# BPC_PWR_MCU.net
KiCad netlist of a schematic drawn in Altium Designer
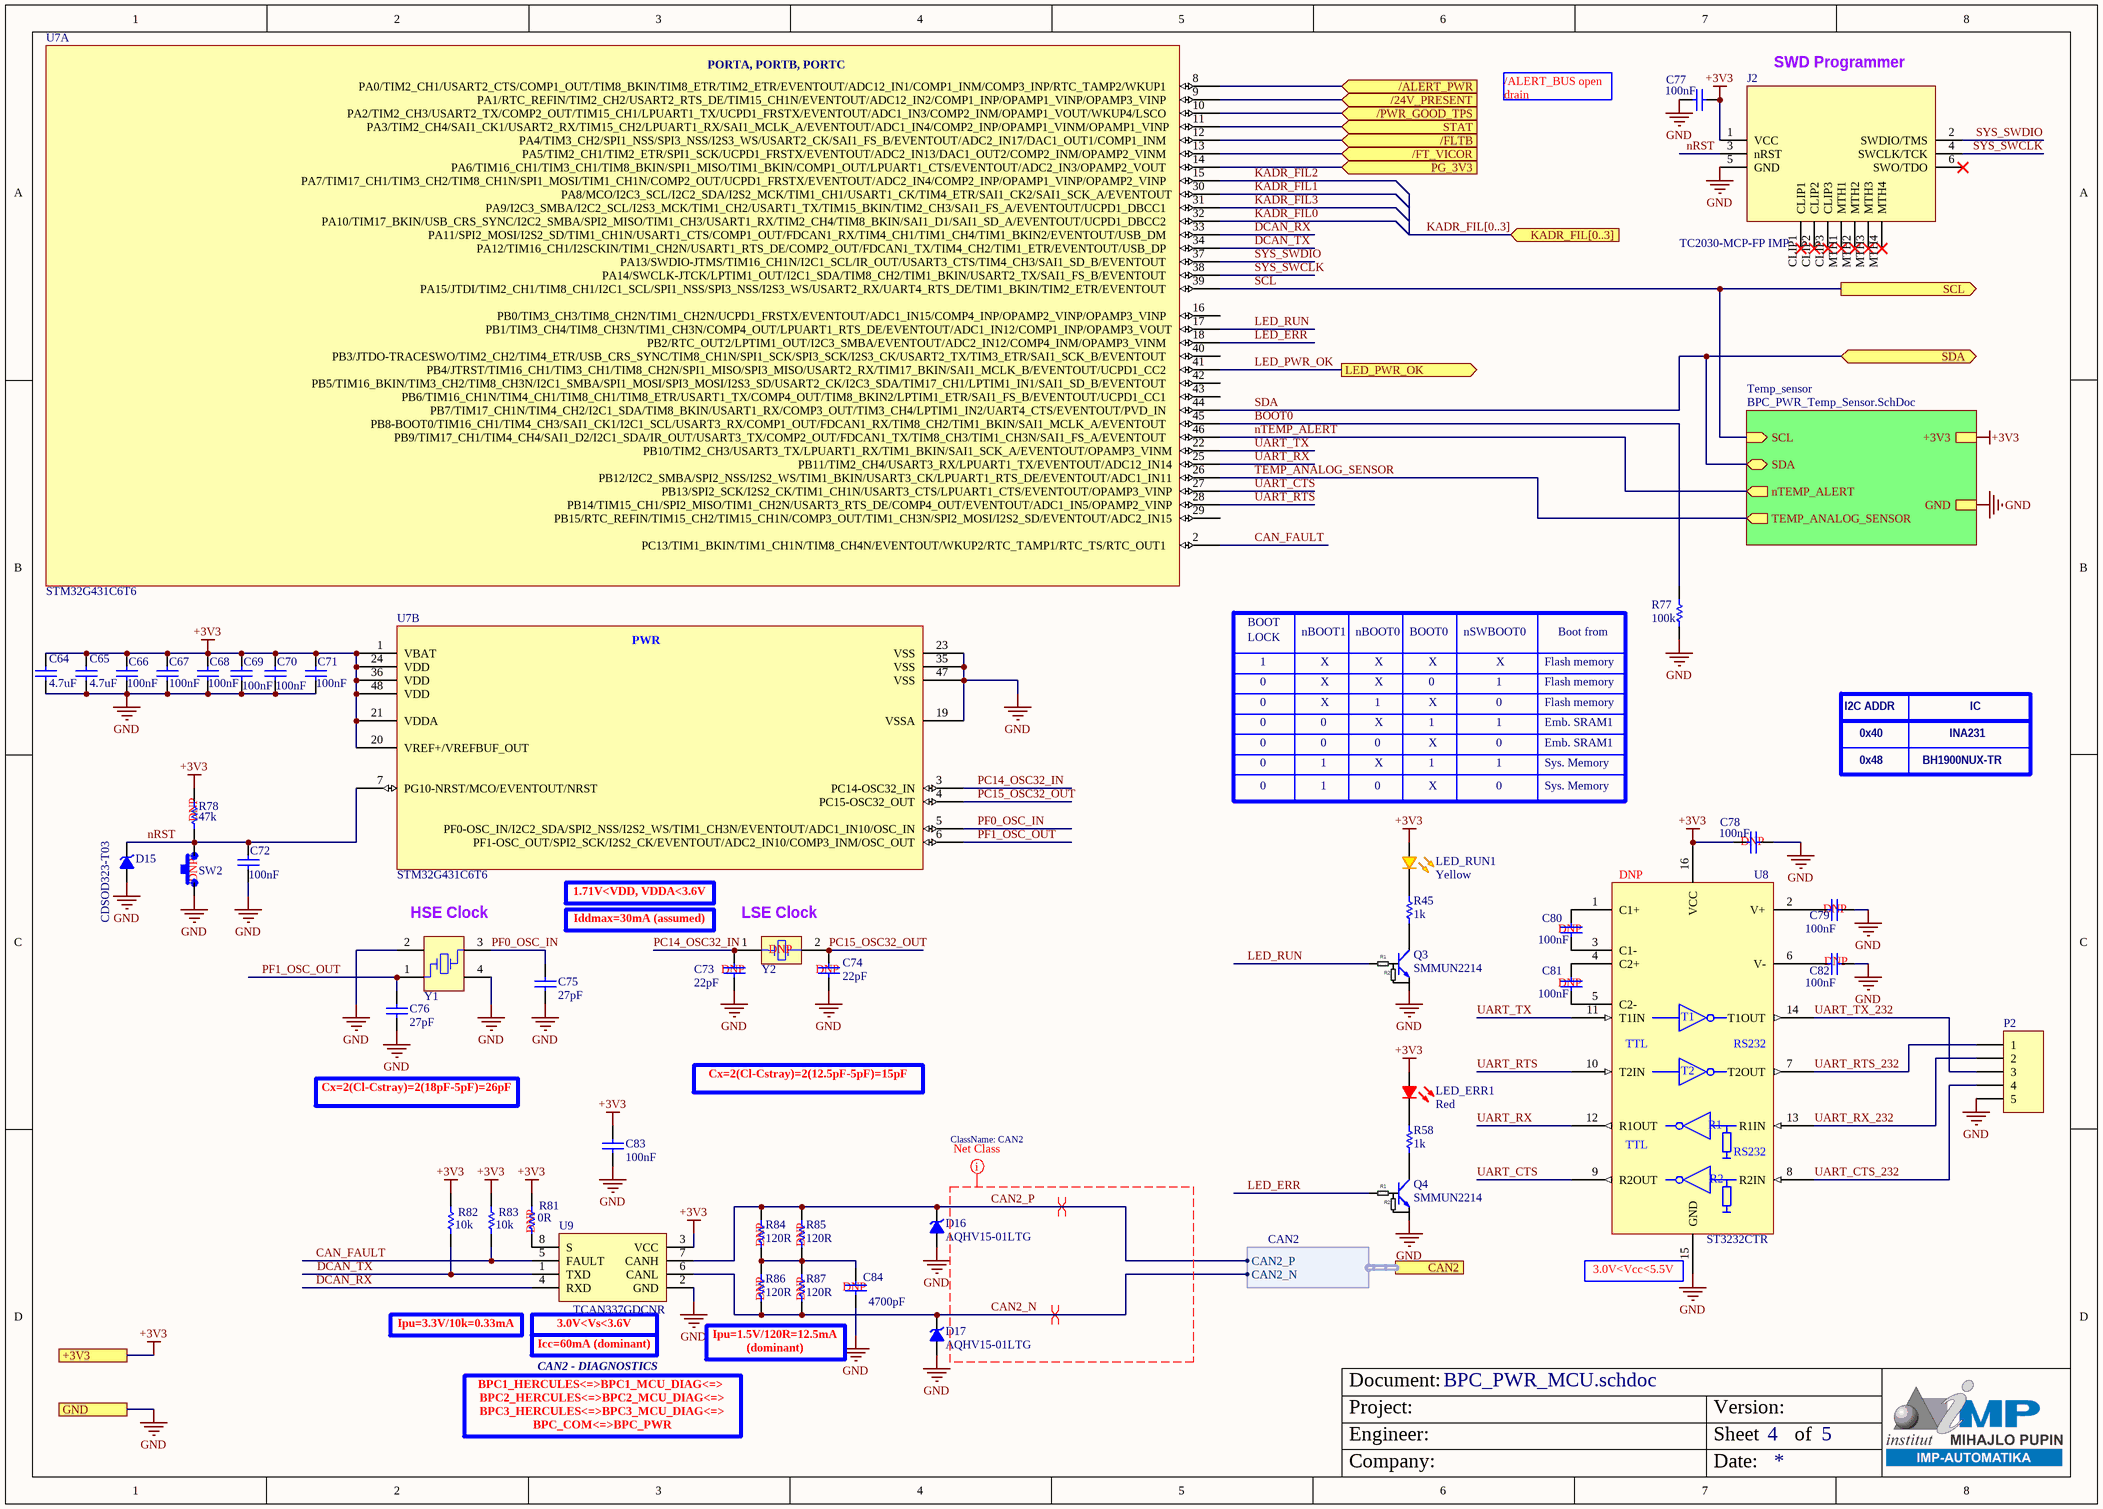
[diagram p0: BPC_PWR_MCU.schdoc]

(export (version "E")
  (design (tool "Eeschema 10.0.6"))
  (components
    (comp (ref "C64")
      (value "Ceramic Capacitor")
      (footprint "C0603L 0.8 MM MS")
      (description "Ceramic Capacitor 4.7uF 10V X5R 0603")
      (fields
        (field (name "DISTRIBUTOR PART NUMBER") "187-CL10A475KP8NNNC")
        (field (name "MANUFACTURER") "Samsung Electro-Mechanics")
        (field (name "DB PARAMETER 1") "4.7uF")
      )
      (libsource (lib "MS IMP Library") (part "Cap Cer 4.7uF 10V X5R 0603 MS"))
    )
    (comp (ref "C65")
      (value "Ceramic Capacitor")
      (footprint "C0603L 0.8 MM MS")
      (description "Ceramic Capacitor 4.7uF 10V X5R 0603")
      (fields
        (field (name "DISTRIBUTOR PART NUMBER") "187-CL10A475KP8NNNC")
        (field (name "MANUFACTURER") "Samsung Electro-Mechanics")
        (field (name "DB PARAMETER 1") "4.7uF")
      )
      (libsource (lib "MS IMP Library") (part "Cap Cer 4.7uF 10V X5R 0603 MS"))
    )
    (comp (ref "C66")
      (value "Ceramic Capacitor")
      (footprint "C0603L 0.8 MM MS")
      (description "Ceramic Capacitor 100nF 50V X7R 0603")
      (fields
        (field (name "DISTRIBUTOR PART NUMBER") "187-CL10B104KB8WPNC")
        (field (name "MANUFACTURER") "Samsung Electro-Mechanics")
        (field (name "CAPACITANCE") "100nF")
      )
      (libsource (lib "MS IMP Library") (part "Cap Cer 100nF 50V X7R 0603 Pt02"))
    )
    (comp (ref "C67")
      (value "Ceramic Capacitor")
      (footprint "C0603L 0.8 MM MS")
      (description "Ceramic Capacitor 100nF 50V X7R 0603")
      (fields
        (field (name "DISTRIBUTOR PART NUMBER") "187-CL10B104KB8WPNC")
        (field (name "MANUFACTURER") "Samsung Electro-Mechanics")
        (field (name "CAPACITANCE") "100nF")
      )
      (libsource (lib "MS IMP Library") (part "Cap Cer 100nF 50V X7R 0603 Pt02"))
    )
    (comp (ref "C68")
      (value "Ceramic Capacitor")
      (footprint "C0603L 0.8 MM MS")
      (description "Ceramic Capacitor 100nF 50V X7R 0603")
      (fields
        (field (name "DISTRIBUTOR PART NUMBER") "187-CL10B104KB8WPNC")
        (field (name "MANUFACTURER") "Samsung Electro-Mechanics")
        (field (name "CAPACITANCE") "100nF")
      )
      (libsource (lib "MS IMP Library") (part "Cap Cer 100nF 50V X7R 0603 Pt02"))
    )
    (comp (ref "C69")
      (value "Ceramic Capacitor")
      (footprint "C0603L 0.8 MM MS")
      (description "Ceramic Capacitor 100nF 50V X7R 0603")
      (fields
        (field (name "DISTRIBUTOR PART NUMBER") "187-CL10B104KB8WPNC")
        (field (name "MANUFACTURER") "Samsung Electro-Mechanics")
        (field (name "CAPACITANCE") "100nF")
      )
      (libsource (lib "MS IMP Library") (part "Cap Cer 100nF 50V X7R 0603 Pt02"))
    )
    (comp (ref "C70")
      (value "Ceramic Capacitor")
      (footprint "C0603L 0.8 MM MS")
      (description "Ceramic Capacitor 100nF 50V X7R 0603")
      (fields
        (field (name "DISTRIBUTOR PART NUMBER") "187-CL10B104KB8WPNC")
        (field (name "MANUFACTURER") "Samsung Electro-Mechanics")
        (field (name "CAPACITANCE") "100nF")
      )
      (libsource (lib "MS IMP Library") (part "Cap Cer 100nF 50V X7R 0603 Pt02"))
    )
    (comp (ref "C71")
      (value "Ceramic Capacitor")
      (footprint "C0603L 0.8 MM MS")
      (description "Ceramic Capacitor 100nF 50V X7R 0603")
      (fields
        (field (name "DISTRIBUTOR PART NUMBER") "187-CL10B104KB8WPNC")
        (field (name "MANUFACTURER") "Samsung Electro-Mechanics")
        (field (name "CAPACITANCE") "100nF")
      )
      (libsource (lib "MS IMP Library") (part "Cap Cer 100nF 50V X7R 0603 Pt02"))
    )
    (comp (ref "C72")
      (value "Ceramic Capacitor")
      (footprint "C0603L 0.8 MM MS")
      (description "Ceramic Capacitor 100nF 50V X7R 0603")
      (fields
        (field (name "DISTRIBUTOR PART NUMBER") "187-CL10B104KB8WPNC")
        (field (name "MANUFACTURER") "Samsung Electro-Mechanics")
        (field (name "CAPACITANCE") "100nF")
      )
      (libsource (lib "MS IMP Library") (part "Cap Cer 100nF 50V X7R 0603 Pt02"))
    )
    (comp (ref "C73")
      (value "Ceramic Capacitor")
      (footprint "C0603L 0.8 MM MS")
      (description "Ceramic Capacitor 22pF 50V C0G_NP0 0603")
      (fields
        (field (name "DISTRIBUTOR PART NUMBER") "478-1167-1-ND")
        (field (name "MANUFACTURER") "AVX Corporation")
        (field (name "POPULATED") "DNP")
        (field (name "CAPACITANCE") "22pF")
      )
      (libsource (lib "MS IMP Library") (part "Cap Cer 22pF 50V C0G_NP0 0603 MS"))
    )
    (comp (ref "C74")
      (value "Ceramic Capacitor")
      (footprint "C0603L 0.8 MM MS")
      (description "Ceramic Capacitor 22pF 50V C0G_NP0 0603")
      (fields
        (field (name "DISTRIBUTOR PART NUMBER") "478-1167-1-ND")
        (field (name "MANUFACTURER") "AVX Corporation")
        (field (name "POPULATED") "DNP")
        (field (name "CAPACITANCE") "22pF")
      )
      (libsource (lib "MS IMP Library") (part "Cap Cer 22pF 50V C0G_NP0 0603 MS"))
    )
    (comp (ref "C75")
      (value "Ceramic Capacitor")
      (footprint "C0603L 0.8 MM MS")
      (description "Ceramic Capacitor 27pF 50V C0G_NP0 0603")
      (fields
        (field (name "DISTRIBUTOR PART NUMBER") "311-1063-1-ND")
        (field (name "MANUFACTURER") "Yageo")
        (field (name "CAPACITANCE") "27pF")
      )
      (libsource (lib "MS IMP Library") (part "Cap Cer 27pF 50V C0G_NP0 0603 MS"))
    )
    (comp (ref "C76")
      (value "Ceramic Capacitor")
      (footprint "C0603L 0.8 MM MS")
      (description "Ceramic Capacitor 27pF 50V C0G_NP0 0603")
      (fields
        (field (name "DISTRIBUTOR PART NUMBER") "311-1063-1-ND")
        (field (name "MANUFACTURER") "Yageo")
        (field (name "CAPACITANCE") "27pF")
      )
      (libsource (lib "MS IMP Library") (part "Cap Cer 27pF 50V C0G_NP0 0603 MS"))
    )
    (comp (ref "C77")
      (value "Ceramic Capacitor")
      (footprint "C0603L 0.8 MM MS")
      (description "Ceramic Capacitor 100nF 50V X7R 0603")
      (fields
        (field (name "DISTRIBUTOR PART NUMBER") "187-CL10B104KB8WPNC")
        (field (name "MANUFACTURER") "Samsung Electro-Mechanics")
        (field (name "CAPACITANCE") "100nF")
      )
      (libsource (lib "MS IMP Library") (part "Cap Cer 100nF 50V X7R 0603 Pt02"))
    )
    (comp (ref "C78")
      (value "Ceramic Capacitor")
      (footprint "C0603L 0.8 MM MS")
      (description "Ceramic Capacitor 100nF 50V X7R 0603")
      (fields
        (field (name "DISTRIBUTOR PART NUMBER") "187-CL10B104KB8WPNC")
        (field (name "MANUFACTURER") "Samsung Electro-Mechanics")
        (field (name "POPULATED") "DNP")
        (field (name "CAPACITANCE") "100nF")
      )
      (libsource (lib "MS IMP Library") (part "Cap Cer 100nF 50V X7R 0603 Pt02"))
    )
    (comp (ref "C79")
      (value "Ceramic Capacitor")
      (footprint "C0603L 0.8 MM MS")
      (description "Ceramic Capacitor 100nF 50V X7R 0603")
      (fields
        (field (name "DISTRIBUTOR PART NUMBER") "187-CL10B104KB8WPNC")
        (field (name "MANUFACTURER") "Samsung Electro-Mechanics")
        (field (name "POPULATED") "DNP")
        (field (name "CAPACITANCE") "100nF")
      )
      (libsource (lib "MS IMP Library") (part "Cap Cer 100nF 50V X7R 0603 Pt02"))
    )
    (comp (ref "C80")
      (value "Ceramic Capacitor")
      (footprint "C0603L 0.8 MM MS")
      (description "Ceramic Capacitor 100nF 50V X7R 0603")
      (fields
        (field (name "DISTRIBUTOR PART NUMBER") "187-CL10B104KB8WPNC")
        (field (name "MANUFACTURER") "Samsung Electro-Mechanics")
        (field (name "POPULATED") "DNP")
        (field (name "CAPACITANCE") "100nF")
      )
      (libsource (lib "MS IMP Library") (part "Cap Cer 100nF 50V X7R 0603 Pt02"))
    )
    (comp (ref "C81")
      (value "Ceramic Capacitor")
      (footprint "C0603L 0.8 MM MS")
      (description "Ceramic Capacitor 100nF 50V X7R 0603")
      (fields
        (field (name "DISTRIBUTOR PART NUMBER") "187-CL10B104KB8WPNC")
        (field (name "MANUFACTURER") "Samsung Electro-Mechanics")
        (field (name "POPULATED") "DNP")
        (field (name "CAPACITANCE") "100nF")
      )
      (libsource (lib "MS IMP Library") (part "Cap Cer 100nF 50V X7R 0603 Pt02"))
    )
    (comp (ref "C82")
      (value "Ceramic Capacitor")
      (footprint "C0603L 0.8 MM MS")
      (description "Ceramic Capacitor 100nF 50V X7R 0603")
      (fields
        (field (name "DISTRIBUTOR PART NUMBER") "187-CL10B104KB8WPNC")
        (field (name "MANUFACTURER") "Samsung Electro-Mechanics")
        (field (name "POPULATED") "DNP")
        (field (name "CAPACITANCE") "100nF")
      )
      (libsource (lib "MS IMP Library") (part "Cap Cer 100nF 50V X7R 0603 Pt02"))
    )
    (comp (ref "C83")
      (value "Ceramic Capacitor")
      (footprint "C0603L 0.8 MM MS")
      (description "Ceramic Capacitor 100nF 50V X7R 0603")
      (fields
        (field (name "DISTRIBUTOR PART NUMBER") "187-CL10B104KB8WPNC")
        (field (name "MANUFACTURER") "Samsung Electro-Mechanics")
        (field (name "CAPACITANCE") "100nF")
      )
      (libsource (lib "MS IMP Library") (part "Cap Cer 100nF 50V X7R 0603 Pt02"))
    )
    (comp (ref "C84")
      (value "Ceramic Capacitor")
      (footprint "C0603L 0.8 MM MS")
      (description "Ceramic Capacitor 4700pF 50V C0G_NP0 0603")
      (fields
        (field (name "DISTRIBUTOR PART NUMBER") "445-6912-1-ND")
        (field (name "MANUFACTURER") "TDK Corporation")
        (field (name "POPULATED") "DNP")
        (field (name "CAPACITANCE") "4700pF")
      )
      (libsource (lib "MS IMP Library") (part "Cap Cer 4700pF 50V C0G_NP0 0603 MS"))
    )
    (comp (ref "D15")
      (value "CDSOD323-T03")
      (footprint "SOD2513X114N")
      (description "TVS Diode 3.3V 19V Udir")
      (fields
        (field (name "DISTRIBUTOR PART NUMBER") "CDSOD323-T03CT-ND")
        (field (name "MANUFACTURER") "Bourns Inc.")
      )
      (libsource (lib "MS IMP Library") (part "Dio TVS Udir 3.3V 19V CDSOD323 MS"))
    )
    (comp (ref "D16")
      (value "AQHV15-01LTG")
      (footprint "AQHV1501LTGC SOD523 MS")
      (description "TVS Diode 15V 300W Unidirectional")
      (fields
        (field (name "DISTRIBUTOR PART NUMBER") "576-AQHV15-01LTG")
        (field (name "MANUFACTURER") "Littelfuse Inc.")
      )
      (libsource (lib "MS IMP Library") (part "Dio TVS Udir 15V 250W AQHV15-01LTG MS"))
    )
    (comp (ref "D17")
      (value "AQHV15-01LTG")
      (footprint "AQHV1501LTGC SOD523 MS")
      (description "TVS Diode 15V 300W Unidirectional")
      (fields
        (field (name "DISTRIBUTOR PART NUMBER") "576-AQHV15-01LTG")
        (field (name "MANUFACTURER") "Littelfuse Inc.")
      )
      (libsource (lib "MS IMP Library") (part "Dio TVS Udir 15V 250W AQHV15-01LTG MS"))
    )
    (comp (ref "J2")
      (value "TC2030-MCP-FP IMP")
      (footprint "TC2030-MCP-FP MS")
      (libsource (lib "MS IMP Library") (part "Prog TC2030-MCP-FP IMP MS"))
    )
    (comp (ref "LED_ERR1")
      (value "Red")
      (footprint "LED Red Mentor 2632.8320 x1")
      (description "LED Mentor 2632.8320 Red x1")
      (fields
        (field (name "DISTRIBUTOR PART NUMBER") "2632.8320 1/8")
        (field (name "MANUFACTURER") "Mentor")
        (field (name "LED COLOR") "Red")
      )
      (libsource (lib "MS IMP Library") (part "LED Mentor 2632.8320 Red x1 MS"))
    )
    (comp (ref "LED_RUN1")
      (value "Yellow")
      (footprint "LED Yellow Mentor 2632.8370 x1 MS")
      (description "LED Mentor 2632.8370 Yellow x1")
      (fields
        (field (name "DISTRIBUTOR PART NUMBER") "2632.8370 1/8")
        (field (name "MANUFACTURER") "Mentor")
        (field (name "LED COLOR") "Yellow")
      )
      (libsource (lib "MS IMP Library") (part "LED Mentor 2632.8370 Yellow x1 MS"))
    )
    (comp (ref "P2")
      (value "Header")
      (footprint "Header 1x5 2.54 12.4/3mm SL 11 124 5 G MS")
      (description "Header 1x5 2.54 12.4/3mm")
      (fields
        (field (name "DISTRIBUTOR PART NUMBER") "SL 11 124 5 G")
        (field (name "MANUFACTURER") "Fischer Elektronik")
      )
      (libsource (lib "MS IMP Library") (part "Con Header 1x5 2.54 12.4/3mm Fischer SL 11 124 5 G"))
    )
    (comp (ref "Q3")
      (value "SMMUN2214")
      (footprint "SOT-23 MS")
      (description "TRANS PREBIAS NPN 50V SOT23")
      (fields
        (field (name "DISTRIBUTOR PART NUMBER") "SMMUN2214LT1GOSCT-ND")
        (field (name "MANUFACTURER") "ON Semiconductor")
      )
      (libsource (lib "MS IMP Library") (part "Tra NPN Prebias MS"))
    )
    (comp (ref "Q4")
      (value "SMMUN2214")
      (footprint "SOT-23 MS")
      (description "TRANS PREBIAS NPN 50V SOT23")
      (fields
        (field (name "DISTRIBUTOR PART NUMBER") "SMMUN2214LT1GOSCT-ND")
        (field (name "MANUFACTURER") "ON Semiconductor")
      )
      (libsource (lib "MS IMP Library") (part "Tra NPN Prebias MS"))
    )
    (comp (ref "R45")
      (value "Resistor")
      (footprint "R0603L 0.45MM MS")
      (description "Resistor 1k 1% 125mW 0603")
      (fields
        (field (name "DISTRIBUTOR PART NUMBER") "MCT0603-1.00K-CFCT-ND")
        (field (name "MANUFACTURER") "Vishay Beyschlag/Draloric/BC Components")
        (field (name "RESISTANCE") "1k")
      )
      (libsource (lib "MS IMP Library") (part "Res 1k 1% 125mW 0603"))
    )
    (comp (ref "R58")
      (value "Resistor")
      (footprint "R0603L 0.45MM MS")
      (description "Resistor 1k 1% 125mW 0603")
      (fields
        (field (name "DISTRIBUTOR PART NUMBER") "MCT0603-1.00K-CFCT-ND")
        (field (name "MANUFACTURER") "Vishay Beyschlag/Draloric/BC Components")
        (field (name "RESISTANCE") "1k")
      )
      (libsource (lib "MS IMP Library") (part "Res 1k 1% 125mW 0603"))
    )
    (comp (ref "R77")
      (value "Resistor")
      (footprint "R0603L 0.45MM MS")
      (description "Resistor 100k 1% 100mW 0603")
      (fields
        (field (name "DISTRIBUTOR PART NUMBER") "RMCF0603FT100KCT-ND")
        (field (name "MANUFACTURER") "Stackpole Electronics Inc")
        (field (name "RESISTANCE") "100k")
      )
      (libsource (lib "MS IMP Library") (part "Res 100k 1% 100mW 0603 Pt02"))
    )
    (comp (ref "R78")
      (value "Resistor")
      (footprint "R0603L 0.45MM MS")
      (description "Resistor 47k 1% 100mW 0603")
      (fields
        (field (name "DISTRIBUTOR PART NUMBER") "YAG3355CT-ND")
        (field (name "MANUFACTURER") "Yageo")
        (field (name "POPULATED") "DNP")
        (field (name "RESISTANCE") "47k")
      )
      (libsource (lib "MS IMP Library") (part "Res 47k 1% 100mW 0603 MS"))
    )
    (comp (ref "R81")
      (value "Resistor")
      (footprint "R0603L 0.45MM MS")
      (description "Resistor  0R 100mW 0603")
      (fields
        (field (name "DISTRIBUTOR PART NUMBER") "RMCF0603ZT0R00CT-ND")
        (field (name "MANUFACTURER") "Stackpole Electronics Inc")
        (field (name "POPULATED") "DNP")
        (field (name "RESISTANCE") "0R")
      )
      (libsource (lib "MS IMP Library") (part "Res 0R 100mW 0603"))
    )
    (comp (ref "R82")
      (value "Resistor")
      (footprint "R0603L 0.45MM MS")
      (description "Resistor 10k 1% 100mW 0603")
      (fields
        (field (name "DISTRIBUTOR PART NUMBER") "13-RC0603FR-1310KLCT-ND")
        (field (name "MANUFACTURER") "Yageo")
        (field (name "RESISTANCE") "10k")
      )
      (libsource (lib "MS IMP Library") (part "Res 10k 1% 100mW 0603"))
    )
    (comp (ref "R83")
      (value "Resistor")
      (footprint "R0603L 0.45MM MS")
      (description "Resistor 10k 1% 100mW 0603")
      (fields
        (field (name "DISTRIBUTOR PART NUMBER") "13-RC0603FR-1310KLCT-ND")
        (field (name "MANUFACTURER") "Yageo")
        (field (name "RESISTANCE") "10k")
      )
      (libsource (lib "MS IMP Library") (part "Res 10k 1% 100mW 0603"))
    )
    (comp (ref "R84")
      (value "Resistor")
      (footprint "0805 R 0.5mm MS")
      (description "Resistor  120R 125mW 0805")
      (fields
        (field (name "DISTRIBUTOR PART NUMBER") "P120ADCT-ND")
        (field (name "MANUFACTURER") "Panasonic Electronic Components")
        (field (name "POPULATED") "DNP")
        (field (name "RESISTANCE") "120R")
      )
      (libsource (lib "MS IMP Library") (part "Res 120R 1% 125mW 0805 MS"))
    )
    (comp (ref "R85")
      (value "Resistor")
      (footprint "0805 R 0.5mm MS")
      (description "Resistor  120R 125mW 0805")
      (fields
        (field (name "DISTRIBUTOR PART NUMBER") "P120ADCT-ND")
        (field (name "MANUFACTURER") "Panasonic Electronic Components")
        (field (name "POPULATED") "DNP")
        (field (name "RESISTANCE") "120R")
      )
      (libsource (lib "MS IMP Library") (part "Res 120R 1% 125mW 0805 MS"))
    )
    (comp (ref "R86")
      (value "Resistor")
      (footprint "0805 R 0.5mm MS")
      (description "Resistor  120R 125mW 0805")
      (fields
        (field (name "DISTRIBUTOR PART NUMBER") "P120ADCT-ND")
        (field (name "MANUFACTURER") "Panasonic Electronic Components")
        (field (name "POPULATED") "DNP")
        (field (name "RESISTANCE") "120R")
      )
      (libsource (lib "MS IMP Library") (part "Res 120R 1% 125mW 0805 MS"))
    )
    (comp (ref "R87")
      (value "Resistor")
      (footprint "0805 R 0.5mm MS")
      (description "Resistor  120R 125mW 0805")
      (fields
        (field (name "DISTRIBUTOR PART NUMBER") "P120ADCT-ND")
        (field (name "MANUFACTURER") "Panasonic Electronic Components")
        (field (name "POPULATED") "DNP")
        (field (name "RESISTANCE") "120R")
      )
      (libsource (lib "MS IMP Library") (part "Res 120R 1% 125mW 0805 MS"))
    )
    (comp (ref "SW2")
      (value "Tactile Switch")
      (footprint "ADTSM3 MS")
      (description "Tactile Switch SPST 0.05A 12VDC")
      (fields
        (field (name "DISTRIBUTOR PART NUMBER") "642-ADTSM32NV")
        (field (name "MANUFACTURER") "Apem")
        (field (name "POPULATED") "DNP")
      )
      (libsource (lib "MS IMP Library") (part "Mech Switch ADTSM32NV MS"))
    )
    (comp (ref "U7")
      (value "STM32G431C6T6")
      (footprint "LQFP48-7x7mm MS")
      (description "IC MCU 32BIT 32KB FLASH 48LQFP")
      (fields
        (field (name "DISTRIBUTOR PART NUMBER") "511-STM32G431C6T6")
        (field (name "MANUFACTURER") "STMicroelectronics")
      )
      (libsource (lib "MS IMP Library") (part "IC MCU STM32G431C6T6 MS"))
    )
    (comp (ref "U8")
      (value "ST3232CTR")
      (footprint "TSSOP16_STM MS")
      (description "IC TRANSCEIVER RS232 FULL 2/2 16TSSOP")
      (fields
        (field (name "DISTRIBUTOR PART NUMBER") "497-6535-1-ND")
        (field (name "MANUFACTURER") "STMicroelectronics")
        (field (name "POPULATED") "DNP")
        (field (name "MANUFACTURER PART NUMBER") "ST3232CTR")
      )
      (libsource (lib "MS IMP Library") (part "IC ST3232CTR MS"))
    )
    (comp (ref "U9")
      (value "TCAN337GDCNR")
      (footprint "SOT65P280X110-8N")
      (description "CAN Interface IC 3.3-V CAN Transceivers with CAN FD SOT 23-8")
      (fields
        (field (name "DISTRIBUTOR PART NUMBER") "595-TCAN337GDCNR")
        (field (name "MANUFACTURER") "Texas Instruments")
      )
      (libsource (lib "MS IMP Library") (part "IC TCAN337GDCNR MS"))
    )
    (comp (ref "Y1")
      (value "Crystal")
      (footprint "ABMM2")
      (description "CRYSTAL 8.0000MHZ 18PF SMD")
      (fields
        (field (name "DISTRIBUTOR PART NUMBER") "535-9628-1-ND")
        (field (name "MANUFACTURER") "ABRACON")
      )
      (libsource (lib "MS IMP Library") (part "Xtal ABMM2-8.000MHZ-E2-T MS"))
    )
    (comp (ref "Y2")
      (value "Crystal")
      (footprint "ABS07W32768kHzD2T")
      (description "Crystal 32.768K HZ 12.5PF SMD")
      (fields
        (field (name "DISTRIBUTOR PART NUMBER") "535-9542-1-ND")
        (field (name "MANUFACTURER") "Abracon LLC")
        (field (name "POPULATED") "DNP")
      )
      (libsource (lib "MS IMP Library") (part "Xtal ABS07-32.768KHZ-T MS"))
    )
  )
  (nets
    (net (code "2") (name "+3V3") (class "Default")
      (node (ref "C64") (pin "1") (pinfunction "1_1") (pintype "passive"))
      (node (ref "C65") (pin "1") (pinfunction "1_1") (pintype "passive"))
      (node (ref "C66") (pin "2") (pinfunction "2_2") (pintype "passive"))
      (node (ref "C67") (pin "2") (pinfunction "2_2") (pintype "passive"))
      (node (ref "C68") (pin "2") (pinfunction "2_2") (pintype "passive"))
      (node (ref "C69") (pin "2") (pinfunction "2_2") (pintype "passive"))
      (node (ref "C70") (pin "2") (pinfunction "2_2") (pintype "passive"))
      (node (ref "C71") (pin "2") (pinfunction "2_2") (pintype "passive"))
      (node (ref "C77") (pin "1") (pinfunction "1_1") (pintype "passive"))
      (node (ref "C78") (pin "2") (pinfunction "2_2") (pintype "passive"))
      (node (ref "C83") (pin "1") (pinfunction "1_1") (pintype "passive"))
      (node (ref "J2") (pin "1") (pinfunction "VCC_1") (pintype "passive"))
      (node (ref "LED_ERR1") (pin "A") (pinfunction "A_A") (pintype "passive"))
      (node (ref "LED_RUN1") (pin "A") (pinfunction "A_A") (pintype "passive"))
      (node (ref "R78") (pin "2") (pinfunction "2_2") (pintype "passive"))
      (node (ref "R81") (pin "2") (pinfunction "2_2") (pintype "passive"))
      (node (ref "R82") (pin "1") (pinfunction "1_1") (pintype "passive"))
      (node (ref "R83") (pin "1") (pinfunction "1_1") (pintype "passive"))
      (node (ref "U7") (pin "1") (pinfunction "VBAT_1") (pintype "power_in"))
      (node (ref "U7") (pin "20") (pinfunction "VREF+/VREFBUF_OUT_20") (pintype "power_in"))
      (node (ref "U7") (pin "21") (pinfunction "VDDA_21") (pintype "power_in"))
      (node (ref "U7") (pin "24") (pinfunction "VDD_24") (pintype "power_in"))
      (node (ref "U7") (pin "36") (pinfunction "VDD_36") (pintype "power_in"))
      (node (ref "U7") (pin "48") (pinfunction "VDD_48") (pintype "power_in"))
      (node (ref "U8") (pin "16") (pinfunction "VCC_16") (pintype "power_in"))
      (node (ref "U9") (pin "3") (pinfunction "VCC_3") (pintype "passive"))
    )
    (net (code "3") (name "/BOOT0") (class "Default")
      (node (ref "R77") (pin "1") (pinfunction "1_1") (pintype "passive"))
      (node (ref "U7") (pin "45") (pinfunction "PB8-BOOT0/TIM16_CH1/TIM4_CH3/SAI1_CK1/I2C1_SCL/USART3_RX/COMP1_OUT/FDCAN1_RX/TIM8_CH2/TIM1_BKIN/SAI1_MCLK_A/EVENTOUT_45") (pintype "bidirectional"))
    )
    (net (code "4") (name "/CAN2_N") (class "Default")
      (node (ref "D17") (pin "1") (pinfunction "K_1") (pintype "passive"))
      (node (ref "R86") (pin "1") (pinfunction "1_1") (pintype "passive"))
      (node (ref "R87") (pin "1") (pinfunction "1_1") (pintype "passive"))
      (node (ref "U9") (pin "6") (pinfunction "CANL_6") (pintype "passive"))
    )
    (net (code "5") (name "/CAN2_P") (class "Default")
      (node (ref "D16") (pin "1") (pinfunction "K_1") (pintype "passive"))
      (node (ref "R84") (pin "2") (pinfunction "2_2") (pintype "passive"))
      (node (ref "R85") (pin "2") (pinfunction "2_2") (pintype "passive"))
      (node (ref "U9") (pin "7") (pinfunction "CANH_7") (pintype "passive"))
    )
    (net (code "6") (name "/CAN_FAULT") (class "Default")
      (node (ref "R83") (pin "2") (pinfunction "2_2") (pintype "passive"))
      (node (ref "U7") (pin "2") (pinfunction "PC13/TIM1_BKIN/TIM1_CH1N/TIM8_CH4N/EVENTOUT/WKUP2/RTC_TAMP1/RTC_TS/RTC_OUT1_2") (pintype "bidirectional"))
      (node (ref "U9") (pin "5") (pinfunction "FAULT_5") (pintype "passive"))
    )
    (net (code "7") (name "/DCAN_RX") (class "Default")
      (node (ref "U7") (pin "33") (pinfunction "PA11/SPI2_MOSI/I2S2_SD/TIM1_CH1N/USART1_CTS/COMP1_OUT/FDCAN1_RX/TIM4_CH1/TIM1_CH4/TIM1_BKIN2/EVENTOUT/USB_DM_33") (pintype "bidirectional"))
      (node (ref "U9") (pin "4") (pinfunction "RXD_4") (pintype "passive"))
    )
    (net (code "8") (name "/DCAN_TX") (class "Default")
      (node (ref "R82") (pin "2") (pinfunction "2_2") (pintype "passive"))
      (node (ref "U7") (pin "34") (pinfunction "PA12/TIM16_CH1/I2SCKIN/TIM1_CH2N/USART1_RTS_DE/COMP2_OUT/FDCAN1_TX/TIM4_CH2/TIM1_ETR/EVENTOUT/USB_DP_34") (pintype "bidirectional"))
      (node (ref "U9") (pin "1") (pinfunction "TXD_1") (pintype "passive"))
    )
    (net (code "9") (name "/KADR_FIL0") (class "Default")
      (node (ref "U7") (pin "32") (pinfunction "PA10/TIM17_BKIN/USB_CRS_SYNC/I2C2_SMBA/SPI2_MISO/TIM1_CH3/USART1_RX/TIM2_CH4/TIM8_BKIN/SAI1_D1/SAI1_SD_A/EVENTOUT/UCPD1_DBCC2_32") (pintype "bidirectional"))
    )
    (net (code "10") (name "/KADR_FIL1") (class "Default")
      (node (ref "U7") (pin "30") (pinfunction "PA8/MCO/I2C3_SCL/I2C2_SDA/I2S2_MCK/TIM1_CH1/USART1_CK/TIM4_ETR/SAI1_CK2/SAI1_SCK_A/EVENTOUT_30") (pintype "bidirectional"))
    )
    (net (code "11") (name "/KADR_FIL2") (class "Default")
      (node (ref "U7") (pin "15") (pinfunction "PA7/TIM17_CH1/TIM3_CH2/TIM8_CH1N/SPI1_MOSI/TIM1_CH1N/COMP2_OUT/UCPD1_FRSTX/EVENTOUT/ADC2_IN4/COMP2_INP/OPAMP1_VINP/OPAMP2_VINP_15") (pintype "bidirectional"))
    )
    (net (code "12") (name "/KADR_FIL3") (class "Default")
      (node (ref "U7") (pin "31") (pinfunction "PA9/I2C3_SMBA/I2C2_SCL/I2S3_MCK/TIM1_CH2/USART1_TX/TIM15_BKIN/TIM2_CH3/SAI1_FS_A/EVENTOUT/UCPD1_DBCC1_31") (pintype "bidirectional"))
    )
    (net (code "14") (name "/LED_ERR") (class "Default")
      (node (ref "Q4") (pin "1") (pintype "passive"))
      (node (ref "U7") (pin "18") (pinfunction "PB2/RTC_OUT2/LPTIM1_OUT/I2C3_SMBA/EVENTOUT/ADC2_IN12/COMP4_INM/OPAMP3_VINM_18") (pintype "bidirectional"))
    )
    (net (code "15") (name "/LED_PWR_OK") (class "Default")
      (node (ref "U7") (pin "41") (pinfunction "PB4/JTRST/TIM16_CH1/TIM3_CH1/TIM8_CH2N/SPI1_MISO/SPI3_MISO/USART2_RX/TIM17_BKIN/SAI1_MCLK_B/EVENTOUT/UCPD1_CC2_41") (pintype "bidirectional"))
    )
    (net (code "16") (name "/LED_RUN") (class "Default")
      (node (ref "Q3") (pin "1") (pintype "passive"))
      (node (ref "U7") (pin "17") (pinfunction "PB1/TIM3_CH4/TIM8_CH3N/TIM1_CH3N/COMP4_OUT/LPUART1_RTS_DE/EVENTOUT/ADC1_IN12/COMP1_INP/OPAMP3_VOUT_17") (pintype "bidirectional"))
    )
    (net (code "17") (name "/PC14_OSC32_IN") (class "Default")
      (node (ref "C73") (pin "1") (pinfunction "1_1") (pintype "passive"))
      (node (ref "U7") (pin "3") (pinfunction "PC14-OSC32_IN_3") (pintype "bidirectional"))
      (node (ref "Y2") (pin "1") (pinfunction "OSC1_1") (pintype "passive"))
    )
    (net (code "18") (name "/PC15_OSC32_OUT") (class "Default")
      (node (ref "C74") (pin "1") (pinfunction "1_1") (pintype "passive"))
      (node (ref "U7") (pin "4") (pinfunction "PC15-OSC32_OUT_4") (pintype "bidirectional"))
      (node (ref "Y2") (pin "2") (pinfunction "COM_2") (pintype "passive"))
    )
    (net (code "19") (name "/PF0_OSC_IN") (class "Default")
      (node (ref "C75") (pin "1") (pinfunction "1_1") (pintype "passive"))
      (node (ref "U7") (pin "5") (pinfunction "PF0-OSC_IN/I2C2_SDA/SPI2_NSS/I2S2_WS/TIM1_CH3N/EVENTOUT/ADC1_IN10/OSC_IN_5") (pintype "bidirectional"))
      (node (ref "Y1") (pin "3") (pinfunction "COM_3") (pintype "passive"))
    )
    (net (code "20") (name "/PF1_OSC_OUT") (class "Default")
      (node (ref "C76") (pin "1") (pinfunction "1_1") (pintype "passive"))
      (node (ref "U7") (pin "6") (pinfunction "PF1-OSC_OUT/SPI2_SCK/I2S2_CK/EVENTOUT/ADC2_IN10/COMP3_INM/OSC_OUT_6") (pintype "bidirectional"))
      (node (ref "Y1") (pin "1") (pinfunction "OSC1_1") (pintype "passive"))
    )
    (net (code "21") (name "/PG_3V3") (class "Default")
      (node (ref "U7") (pin "14") (pinfunction "PA6/TIM16_CH1/TIM3_CH1/TIM8_BKIN/SPI1_MISO/TIM1_BKIN/COMP1_OUT/LPUART1_CTS/EVENTOUT/ADC2_IN3/OPAMP2_VOUT_14") (pintype "bidirectional"))
    )
    (net (code "22") (name "/SCL") (class "Default")
      (node (ref "U7") (pin "39") (pinfunction "PA15/JTDI/TIM2_CH1/TIM8_CH1/I2C1_SCL/SPI1_NSS/SPI3_NSS/I2S3_WS/USART2_RX/UART4_RTS_DE/TIM1_BKIN/TIM2_ETR/EVENTOUT_39") (pintype "bidirectional"))
    )
    (net (code "23") (name "/SDA") (class "Default")
      (node (ref "U7") (pin "44") (pinfunction "PB7/TIM17_CH1N/TIM4_CH2/I2C1_SDA/TIM8_BKIN/USART1_RX/COMP3_OUT/TIM3_CH4/LPTIM1_IN2/UART4_CTS/EVENTOUT/PVD_IN_44") (pintype "bidirectional"))
    )
    (net (code "24") (name "/STAT") (class "Default")
      (node (ref "U7") (pin "11") (pinfunction "PA3/TIM2_CH4/SAI1_CK1/USART2_RX/TIM15_CH2/LPUART1_RX/SAI1_MCLK_A/EVENTOUT/ADC1_IN4/COMP2_INP/OPAMP1_VINM/OPAMP1_VINP_11") (pintype "bidirectional"))
    )
    (net (code "25") (name "/SYS_SWCLK") (class "Default")
      (node (ref "J2") (pin "4") (pinfunction "SWCLK/TCK_4") (pintype "passive"))
      (node (ref "U7") (pin "38") (pinfunction "PA14/SWCLK-JTCK/LPTIM1_OUT/I2C1_SDA/TIM8_CH2/TIM1_BKIN/USART2_TX/SAI1_FS_B/EVENTOUT_38") (pintype "bidirectional"))
    )
    (net (code "26") (name "/SYS_SWDIO") (class "Default")
      (node (ref "J2") (pin "2") (pinfunction "SWDIO/TMS_2") (pintype "passive"))
      (node (ref "U7") (pin "37") (pinfunction "PA13/SWDIO-JTMS/TIM16_CH1N/I2C1_SCL/IR_OUT/USART3_CTS/TIM4_CH3/SAI1_SD_B/EVENTOUT_37") (pintype "bidirectional"))
    )
    (net (code "27") (name "/TEMP_ANALOG_SENSOR") (class "Default")
      (node (ref "U7") (pin "26") (pinfunction "PB12/I2C2_SMBA/SPI2_NSS/I2S2_WS/TIM1_BKIN/USART3_CK/LPUART1_RTS_DE/EVENTOUT/ADC1_IN11_26") (pintype "bidirectional"))
    )
    (net (code "28") (name "/UART_CTS") (class "Default")
      (node (ref "U7") (pin "27") (pinfunction "PB13/SPI2_SCK/I2S2_CK/TIM1_CH1N/USART3_CTS/LPUART1_CTS/EVENTOUT/OPAMP3_VINP_27") (pintype "bidirectional"))
      (node (ref "U8") (pin "9") (pinfunction "R2OUT_9") (pintype "output"))
    )
    (net (code "29") (name "/UART_CTS_232") (class "Default")
      (node (ref "P2") (pin "4") (pinfunction "4_4") (pintype "passive"))
      (node (ref "U8") (pin "8") (pinfunction "R2IN_8") (pintype "input"))
    )
    (net (code "30") (name "/UART_RTS") (class "Default")
      (node (ref "U7") (pin "28") (pinfunction "PB14/TIM15_CH1/SPI2_MISO/TIM1_CH2N/USART3_RTS_DE/COMP4_OUT/EVENTOUT/ADC1_IN5/OPAMP2_VINP_28") (pintype "bidirectional"))
      (node (ref "U8") (pin "10") (pinfunction "T2IN_10") (pintype "input"))
    )
    (net (code "31") (name "/UART_RTS_232") (class "Default")
      (node (ref "P2") (pin "1") (pinfunction "1_1") (pintype "passive"))
      (node (ref "U8") (pin "7") (pinfunction "T2OUT_7") (pintype "output"))
    )
    (net (code "32") (name "/UART_RX") (class "Default")
      (node (ref "U7") (pin "25") (pinfunction "PB11/TIM2_CH4/USART3_RX/LPUART1_TX/EVENTOUT/ADC12_IN14_25") (pintype "bidirectional"))
      (node (ref "U8") (pin "12") (pinfunction "R1OUT_12") (pintype "output"))
    )
    (net (code "33") (name "/UART_RX_232") (class "Default")
      (node (ref "P2") (pin "2") (pinfunction "2_2") (pintype "passive"))
      (node (ref "U8") (pin "13") (pinfunction "R1IN_13") (pintype "input"))
    )
    (net (code "34") (name "/UART_TX") (class "Default")
      (node (ref "U7") (pin "22") (pinfunction "PB10/TIM2_CH3/USART3_TX/LPUART1_RX/TIM1_BKIN/SAI1_SCK_A/EVENTOUT/OPAMP3_VINM_22") (pintype "bidirectional"))
      (node (ref "U8") (pin "11") (pinfunction "T1IN_11") (pintype "input"))
    )
    (net (code "35") (name "/UART_TX_232") (class "Default")
      (node (ref "P2") (pin "3") (pinfunction "3_3") (pintype "passive"))
      (node (ref "U8") (pin "14") (pinfunction "T1OUT_14") (pintype "output"))
    )
    (net (code "36") (name "/nRST") (class "Default")
      (node (ref "C72") (pin "2") (pinfunction "2_2") (pintype "passive"))
      (node (ref "D15") (pin "K") (pinfunction "K_K") (pintype "passive"))
      (node (ref "J2") (pin "3") (pinfunction "nRST_3") (pintype "passive"))
      (node (ref "R78") (pin "1") (pinfunction "1_1") (pintype "passive"))
      (node (ref "SW2") (pin "2") (pinfunction "2_2") (pintype "passive"))
      (node (ref "U7") (pin "7") (pinfunction "PG10-NRST/MCO/EVENTOUT/NRST_7") (pintype "bidirectional"))
    )
    (net (code "37") (name "/nTEMP_ALERT") (class "Default")
      (node (ref "U7") (pin "46") (pinfunction "PB9/TIM17_CH1/TIM4_CH4/SAI1_D2/I2C1_SDA/IR_OUT/USART3_TX/COMP2_OUT/FDCAN1_TX/TIM8_CH3/TIM1_CH3N/SAI1_FS_A/EVENTOUT_46") (pintype "bidirectional"))
    )
    (net (code "39") (name "/{slash}24V_PRESENT") (class "Default")
      (node (ref "U7") (pin "9") (pinfunction "PA1/RTC_REFIN/TIM2_CH2/USART2_RTS_DE/TIM15_CH1N/EVENTOUT/ADC12_IN2/COMP1_INP/OPAMP1_VINP/OPAMP3_VINP_9") (pintype "bidirectional"))
    )
    (net (code "40") (name "/{slash}ALERT_PWR") (class "Default")
      (node (ref "U7") (pin "8") (pinfunction "PA0/TIM2_CH1/USART2_CTS/COMP1_OUT/TIM8_BKIN/TIM8_ETR/TIM2_ETR/EVENTOUT/ADC12_IN1/COMP1_INM/COMP3_INP/RTC_TAMP2/WKUP1_8") (pintype "bidirectional"))
    )
    (net (code "41") (name "/{slash}FLTB") (class "Default")
      (node (ref "U7") (pin "12") (pinfunction "PA4/TIM3_CH2/SPI1_NSS/SPI3_NSS/I2S3_WS/USART2_CK/SAI1_FS_B/EVENTOUT/ADC2_IN17/DAC1_OUT1/COMP1_INM_12") (pintype "bidirectional"))
    )
    (net (code "42") (name "/{slash}FT_VICOR") (class "Default")
      (node (ref "U7") (pin "13") (pinfunction "PA5/TIM2_CH1/TIM2_ETR/SPI1_SCK/UCPD1_FRSTX/EVENTOUT/ADC2_IN13/DAC1_OUT2/COMP2_INM/OPAMP2_VINM_13") (pintype "bidirectional"))
    )
    (net (code "43") (name "/{slash}PWR_GOOD_TPS") (class "Default")
      (node (ref "U7") (pin "10") (pinfunction "PA2/TIM2_CH3/USART2_TX/COMP2_OUT/TIM15_CH1/LPUART1_TX/UCPD1_FRSTX/EVENTOUT/ADC1_IN3/COMP2_INM/OPAMP1_VOUT/WKUP4/LSCO_10") (pintype "bidirectional"))
    )
    (net (code "44") (name "GND") (class "Default")
      (node (ref "C64") (pin "2") (pinfunction "2_2") (pintype "passive"))
      (node (ref "C65") (pin "2") (pinfunction "2_2") (pintype "passive"))
      (node (ref "C66") (pin "1") (pinfunction "1_1") (pintype "passive"))
      (node (ref "C67") (pin "1") (pinfunction "1_1") (pintype "passive"))
      (node (ref "C68") (pin "1") (pinfunction "1_1") (pintype "passive"))
      (node (ref "C69") (pin "1") (pinfunction "1_1") (pintype "passive"))
      (node (ref "C70") (pin "1") (pinfunction "1_1") (pintype "passive"))
      (node (ref "C71") (pin "1") (pinfunction "1_1") (pintype "passive"))
      (node (ref "C72") (pin "1") (pinfunction "1_1") (pintype "passive"))
      (node (ref "C73") (pin "2") (pinfunction "2_2") (pintype "passive"))
      (node (ref "C74") (pin "2") (pinfunction "2_2") (pintype "passive"))
      (node (ref "C75") (pin "2") (pinfunction "2_2") (pintype "passive"))
      (node (ref "C76") (pin "2") (pinfunction "2_2") (pintype "passive"))
      (node (ref "C77") (pin "2") (pinfunction "2_2") (pintype "passive"))
      (node (ref "C78") (pin "1") (pinfunction "1_1") (pintype "passive"))
      (node (ref "C79") (pin "1") (pinfunction "1_1") (pintype "passive"))
      (node (ref "C82") (pin "1") (pinfunction "1_1") (pintype "passive"))
      (node (ref "C83") (pin "2") (pinfunction "2_2") (pintype "passive"))
      (node (ref "C84") (pin "2") (pinfunction "2_2") (pintype "passive"))
      (node (ref "D15") (pin "A") (pinfunction "A_A") (pintype "passive"))
      (node (ref "D16") (pin "2") (pinfunction "A_2") (pintype "passive"))
      (node (ref "D17") (pin "2") (pinfunction "A_2") (pintype "passive"))
      (node (ref "J2") (pin "5") (pinfunction "GND_5") (pintype "passive"))
      (node (ref "P2") (pin "5") (pinfunction "5_5") (pintype "passive"))
      (node (ref "Q3") (pin "2") (pintype "passive"))
      (node (ref "Q4") (pin "2") (pintype "passive"))
      (node (ref "R77") (pin "2") (pinfunction "2_2") (pintype "passive"))
      (node (ref "SW2") (pin "1") (pinfunction "1_1") (pintype "passive"))
      (node (ref "U7") (pin "19") (pinfunction "VSSA_19") (pintype "power_in"))
      (node (ref "U7") (pin "23") (pinfunction "VSS_23") (pintype "power_in"))
      (node (ref "U7") (pin "35") (pinfunction "VSS_35") (pintype "power_in"))
      (node (ref "U7") (pin "47") (pinfunction "VSS_47") (pintype "power_in"))
      (node (ref "U8") (pin "15") (pinfunction "GND_15") (pintype "power_in"))
      (node (ref "U9") (pin "2") (pinfunction "GND_2") (pintype "passive"))
      (node (ref "Y1") (pin "2") (pinfunction "COM_2") (pintype "passive"))
      (node (ref "Y1") (pin "4") (pinfunction "OSC2_4") (pintype "passive"))
    )
    (net (code "45") (name "Net-(C84-Pad1)") (class "Default")
      (node (ref "C84") (pin "1") (pinfunction "1_1") (pintype "passive"))
      (node (ref "R84") (pin "1") (pinfunction "1_1") (pintype "passive"))
      (node (ref "R85") (pin "1") (pinfunction "1_1") (pintype "passive"))
      (node (ref "R86") (pin "2") (pinfunction "2_2") (pintype "passive"))
      (node (ref "R87") (pin "2") (pinfunction "2_2") (pintype "passive"))
    )
    (net (code "46") (name "Net-(LED_ERR1-PadK)") (class "Default")
      (node (ref "LED_ERR1") (pin "K") (pinfunction "K_K") (pintype "passive"))
      (node (ref "R58") (pin "2") (pinfunction "2_2") (pintype "passive"))
    )
    (net (code "47") (name "Net-(LED_RUN1-PadK)") (class "Default")
      (node (ref "LED_RUN1") (pin "K") (pinfunction "K_K") (pintype "passive"))
      (node (ref "R45") (pin "2") (pinfunction "2_2") (pintype "passive"))
    )
    (net (code "48") (name "Net-(Q3-Pad3)") (class "Default")
      (node (ref "Q3") (pin "3") (pintype "passive"))
      (node (ref "R45") (pin "1") (pinfunction "1_1") (pintype "passive"))
    )
    (net (code "49") (name "Net-(Q4-Pad3)") (class "Default")
      (node (ref "Q4") (pin "3") (pintype "passive"))
      (node (ref "R58") (pin "1") (pinfunction "1_1") (pintype "passive"))
    )
    (net (code "50") (name "Net-(U8-C1+)") (class "Default")
      (node (ref "C80") (pin "2") (pinfunction "2_2") (pintype "passive"))
      (node (ref "U8") (pin "1") (pinfunction "C1+_1") (pintype "passive"))
    )
    (net (code "51") (name "Net-(U8-C1-)") (class "Default")
      (node (ref "C80") (pin "1") (pinfunction "1_1") (pintype "passive"))
      (node (ref "U8") (pin "3") (pinfunction "C1-_3") (pintype "passive"))
    )
    (net (code "52") (name "Net-(U8-C2+)") (class "Default")
      (node (ref "C81") (pin "2") (pinfunction "2_2") (pintype "passive"))
      (node (ref "U8") (pin "4") (pinfunction "C2+_4") (pintype "passive"))
    )
    (net (code "53") (name "Net-(U8-C2-)") (class "Default")
      (node (ref "C81") (pin "1") (pinfunction "1_1") (pintype "passive"))
      (node (ref "U8") (pin "5") (pinfunction "C2-_5") (pintype "passive"))
    )
    (net (code "54") (name "Net-(U8-V+)") (class "Default")
      (node (ref "C79") (pin "2") (pinfunction "2_2") (pintype "passive"))
      (node (ref "U8") (pin "2") (pinfunction "V+_2") (pintype "passive"))
    )
    (net (code "55") (name "Net-(U8-V-)") (class "Default")
      (node (ref "C82") (pin "2") (pinfunction "2_2") (pintype "passive"))
      (node (ref "U8") (pin "6") (pinfunction "V-_6") (pintype "passive"))
    )
    (net (code "56") (name "Net-(U9-S)") (class "Default")
      (node (ref "R81") (pin "1") (pinfunction "1_1") (pintype "passive"))
      (node (ref "U9") (pin "8") (pinfunction "S_8") (pintype "passive"))
    )
    (net (code "57") (name "unconnected-(J2-PadCLIP1)") (class "Default")
      (node (ref "J2") (pin "CLIP1") (pinfunction "CLIP1_CLIP1") (pintype "passive+no_connect"))
    )
    (net (code "58") (name "unconnected-(J2-PadCLIP2)") (class "Default")
      (node (ref "J2") (pin "CLIP2") (pinfunction "CLIP2_CLIP2") (pintype "passive+no_connect"))
    )
    (net (code "59") (name "unconnected-(J2-PadCLIP3)") (class "Default")
      (node (ref "J2") (pin "CLIP3") (pinfunction "CLIP3_CLIP3") (pintype "passive+no_connect"))
    )
    (net (code "60") (name "unconnected-(J2-PadMTH1)") (class "Default")
      (node (ref "J2") (pin "MTH1") (pinfunction "MTH1_MTH1") (pintype "passive+no_connect"))
    )
    (net (code "61") (name "unconnected-(J2-PadMTH2)") (class "Default")
      (node (ref "J2") (pin "MTH2") (pinfunction "MTH2_MTH2") (pintype "passive+no_connect"))
    )
    (net (code "62") (name "unconnected-(J2-PadMTH3)") (class "Default")
      (node (ref "J2") (pin "MTH3") (pinfunction "MTH3_MTH3") (pintype "passive+no_connect"))
    )
    (net (code "63") (name "unconnected-(J2-PadMTH4)") (class "Default")
      (node (ref "J2") (pin "MTH4") (pinfunction "MTH4_MTH4") (pintype "passive+no_connect"))
    )
    (net (code "64") (name "unconnected-(J2-SWO{slash}TDO-Pad6)") (class "Default")
      (node (ref "J2") (pin "6") (pinfunction "SWO/TDO_6") (pintype "passive+no_connect"))
    )
    (net (code "65") (name "unconnected-(U7A-PB0{slash}TIM3_CH3{slash}TIM8_CH2N{slash}TIM1_CH2N{slash}UCPD1_FRSTX{slash}EVENTOUT{slash}ADC1_IN15{slash}COMP4_INP{slash}OPAMP2_VINP{slash}OPAMP3_VINP-Pad16)") (class "Default")
      (node (ref "U7") (pin "16") (pinfunction "PB0/TIM3_CH3/TIM8_CH2N/TIM1_CH2N/UCPD1_FRSTX/EVENTOUT/ADC1_IN15/COMP4_INP/OPAMP2_VINP/OPAMP3_VINP_16") (pintype "bidirectional"))
    )
    (net (code "66") (name "unconnected-(U7A-PB3{slash}JTDO-TRACESWO{slash}TIM2_CH2{slash}TIM4_ETR{slash}USB_CRS_SYNC{slash}TIM8_CH1N{slash}SPI1_SCK{slash}SPI3_SCK{slash}I2S3_CK{slash}USART2_TX{slash}TIM3_ETR{slash}SAI1_SCK_B{slash}EVENTOUT-Pad40)") (class "Default")
      (node (ref "U7") (pin "40") (pinfunction "PB3/JTDO-TRACESWO/TIM2_CH2/TIM4_ETR/USB_CRS_SYNC/TIM8_CH1N/SPI1_SCK/SPI3_SCK/I2S3_CK/USART2_TX/TIM3_ETR/SAI1_SCK_B/EVENTOUT_40") (pintype "bidirectional"))
    )
    (net (code "67") (name "unconnected-(U7A-PB5{slash}TIM16_BKIN{slash}TIM3_CH2{slash}TIM8_CH3N{slash}I2C1_SMBA{slash}SPI1_MOSI{slash}SPI3_MOSI{slash}I2S3_SD{slash}USART2_CK{slash}I2C3_SDA{slash}TIM17_CH1{slash}LPTIM1_IN1{slash}SAI1_SD_B{slash}EVENTOUT-Pad42)") (class "Default")
      (node (ref "U7") (pin "42") (pinfunction "PB5/TIM16_BKIN/TIM3_CH2/TIM8_CH3N/I2C1_SMBA/SPI1_MOSI/SPI3_MOSI/I2S3_SD/USART2_CK/I2C3_SDA/TIM17_CH1/LPTIM1_IN1/SAI1_SD_B/EVENTOUT_42") (pintype "bidirectional"))
    )
    (net (code "68") (name "unconnected-(U7A-PB6{slash}TIM16_CH1N{slash}TIM4_CH1{slash}TIM8_CH1{slash}TIM8_ETR{slash}USART1_TX{slash}COMP4_OUT{slash}TIM8_BKIN2{slash}LPTIM1_ETR{slash}SAI1_FS_B{slash}EVENTOUT{slash}UCPD1_CC1-Pad43)") (class "Default")
      (node (ref "U7") (pin "43") (pinfunction "PB6/TIM16_CH1N/TIM4_CH1/TIM8_CH1/TIM8_ETR/USART1_TX/COMP4_OUT/TIM8_BKIN2/LPTIM1_ETR/SAI1_FS_B/EVENTOUT/UCPD1_CC1_43") (pintype "bidirectional"))
    )
    (net (code "69") (name "unconnected-(U7A-PB15{slash}RTC_REFIN{slash}TIM15_CH2{slash}TIM15_CH1N{slash}COMP3_OUT{slash}TIM1_CH3N{slash}SPI2_MOSI{slash}I2S2_SD{slash}EVENTOUT{slash}ADC2_IN15-Pad29)") (class "Default")
      (node (ref "U7") (pin "29") (pinfunction "PB15/RTC_REFIN/TIM15_CH2/TIM15_CH1N/COMP3_OUT/TIM1_CH3N/SPI2_MOSI/I2S2_SD/EVENTOUT/ADC2_IN15_29") (pintype "bidirectional"))
    )
  )
)
